# NBBC95.net
KiCad netlist of a schematic drawn in Altium Designer
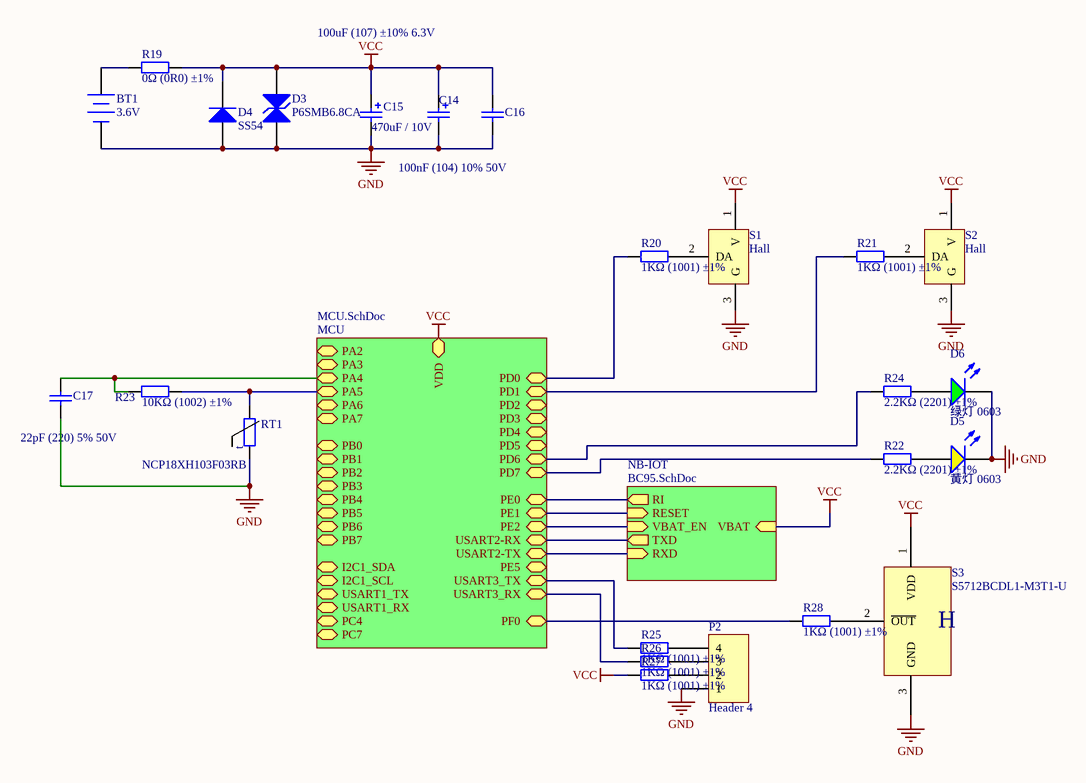
[diagram p0: NBBC95水表.SchDoc]

(export (version "E")
  (design (tool "Eeschema 10.0.6"))
  (components
    (comp (ref "BT1")
      (value "3.6V")
      (footprint "电池连接焊线")
      (description "功率型锂电池")
      (fields (field (name "PUBLISHER") "Altium Limited"))
      (libsource (lib "Miscellaneous Devices") (part "Battery"))
    )
    (comp (ref "C14")
      (value "100uF (107) ±10% 6.3V")
      (footprint "CASE-B_3528")
      (description "钽电容")
      (libsource (lib "Miscellaneous Devices LC") (part "3528 100uF (107) 10% 6.3V"))
    )
    (comp (ref "C15")
      (value "470uF / 10V")
      (footprint "CASE-E_7343")
      (description "钽电容")
      (libsource (lib "CAP") (part "法拉电容 0.5F"))
    )
    (comp (ref "C16")
      (value "100nF (104) 10% 50V")
      (footprint "0603_C")
      (description "贴片电容")
      (libsource (lib "Miscellaneous Devices LC") (part "0603 100nF (104) 10% 50V"))
    )
    (comp (ref "C17")
      (value "22pF (220) 5% 50V")
      (footprint "0603_C")
      (description "贴片电容")
      (libsource (lib "Miscellaneous Devices LC") (part "0603 22pF (220) 5% 50V"))
    )
    (comp (ref "D3")
      (value "P6SMB6.8CA")
      (footprint "SMB(DO-214AA)_S1")
      (description "TVS")
      (libsource (lib "Miscellaneous Devices LC") (part "SMB/DO-214AA P6SMB6.8CA"))
    )
    (comp (ref "D4")
      (value "SS54")
      (footprint "SMA(DO-214AC)_S1")
      (description "二极管")
      (libsource (lib "Miscellaneous Devices LC") (part "SMA(DO-214AC) SS54"))
    )
    (comp (ref "D5")
      (value "黄灯 0603")
      (footprint "0603_LED_S1")
      (description "发光二极管")
      (libsource (lib "Miscellaneous Devices LC") (part "0603 黄灯"))
    )
    (comp (ref "D6")
      (value "绿灯 0603")
      (footprint "0603_LED_S1")
      (description "发光二极管")
      (libsource (lib "Miscellaneous Devices LC") (part "0603 绿灯"))
    )
    (comp (ref "P2")
      (value "Header 4")
      (footprint "HDR1X4")
      (description "Header, 4-Pin")
      (fields (field (name "PUBLISHER") "Altium Limited"))
      (libsource (lib "Miscellaneous Connectors") (part "Header 4"))
    )
    (comp (ref "R19")
      (value "0Ω (0R0) ±1%")
      (footprint "0805_R")
      (description "贴片电阻")
      (libsource (lib "Miscellaneous Devices LC") (part "0805 0Ω (0R0) 1%"))
    )
    (comp (ref "R20")
      (value "1KΩ (1001) ±1%")
      (footprint "0603_R")
      (description "贴片电阻")
      (libsource (lib "Miscellaneous Devices LC") (part "0603 1KΩ (1001) 1%"))
    )
    (comp (ref "R21")
      (value "1KΩ (1001) ±1%")
      (footprint "0603_R")
      (description "贴片电阻")
      (libsource (lib "Miscellaneous Devices LC") (part "0603 1KΩ (1001) 1%"))
    )
    (comp (ref "R22")
      (value "2.2KΩ (2201) ±1%")
      (footprint "0603_R")
      (description "贴片电阻")
      (libsource (lib "Miscellaneous Devices LC") (part "0603 2.2KΩ (2201) 1%"))
    )
    (comp (ref "R23")
      (value "10KΩ (1002) ±1%")
      (footprint "0603_R")
      (description "贴片电阻")
      (libsource (lib "Miscellaneous Devices LC") (part "0603 10KΩ (1002) 1%"))
    )
    (comp (ref "R24")
      (value "2.2KΩ (2201) ±1%")
      (footprint "0603_R")
      (description "贴片电阻")
      (libsource (lib "Miscellaneous Devices LC") (part "0603 2.2KΩ (2201) 1%"))
    )
    (comp (ref "R25")
      (value "1KΩ (1001) ±1%")
      (footprint "0603_R")
      (description "贴片电阻")
      (libsource (lib "") (part "0603 1KΩ (1001) 1%_1"))
    )
    (comp (ref "R26")
      (value "1KΩ (1001) ±1%")
      (footprint "0603_R")
      (description "贴片电阻")
      (libsource (lib "") (part "0603 1KΩ (1001) 1%_1"))
    )
    (comp (ref "R27")
      (value "1KΩ (1001) ±1%")
      (footprint "0603_R")
      (description "贴片电阻")
      (libsource (lib "") (part "0603 1KΩ (1001) 1%_1"))
    )
    (comp (ref "R28")
      (value "1KΩ (1001) ±1%")
      (footprint "0603_R")
      (description "贴片电阻")
      (libsource (lib "Miscellaneous Devices LC") (part "0603 1KΩ (1001) 1%"))
    )
    (comp (ref "RT1")
      (value "NCP18XH103F03RB")
      (footprint "0603_R")
      (description "热敏电阻")
      (libsource (lib "RES") (part "NCP18XH103F03RB"))
    )
    (comp (ref "S1")
      (value "Hall")
      (footprint "霍尔转接板")
      (description "霍尔开关转接板")
      (libsource (lib "NB") (part "霍尔开关转接板"))
    )
    (comp (ref "S2")
      (value "Hall")
      (footprint "霍尔转接板")
      (description "霍尔开关转接板")
      (libsource (lib "NB") (part "霍尔开关转接板"))
    )
    (comp (ref "S3") (value "S5712BCDL1-M3T1-U") (footprint "SOT-23") (libsource (lib "分立元件") (part "S5712")))
  )
  (nets
    (net (code "5") (name "/PA4") (class "Default")
      (node (ref "C17") (pin "2") (pinfunction "2_2") (pintype "passive"))
      (node (ref "R23") (pin "1") (pinfunction "1_1") (pintype "passive"))
    )
    (net (code "6") (name "/PA5") (class "Default")
      (node (ref "R23") (pin "2") (pinfunction "2_2") (pintype "passive"))
      (node (ref "RT1") (pin "2") (pinfunction "2_2") (pintype "passive"))
    )
    (net (code "19") (name "/PD0") (class "Default")
      (node (ref "R20") (pin "1") (pinfunction "1_1") (pintype "passive"))
    )
    (net (code "20") (name "/PD1") (class "Default")
      (node (ref "R21") (pin "1") (pinfunction "1_1") (pintype "passive"))
    )
    (net (code "25") (name "/PD6") (class "Default")
      (node (ref "R24") (pin "1") (pinfunction "1_1") (pintype "passive"))
    )
    (net (code "26") (name "/PD7") (class "Default")
      (node (ref "R22") (pin "1") (pinfunction "1_1") (pintype "passive"))
    )
    (net (code "30") (name "/PF0") (class "Default")
      (node (ref "R28") (pin "1") (pinfunction "1_1") (pintype "passive"))
    )
    (net (code "36") (name "/USART3_RX") (class "Default")
      (node (ref "R26") (pin "2") (pinfunction "2_2") (pintype "passive"))
    )
    (net (code "37") (name "/USART3_TX") (class "Default")
      (node (ref "R25") (pin "2") (pinfunction "2_2") (pintype "passive"))
    )
    (net (code "38") (name "GND") (class "Default")
      (node (ref "BT1") (pin "2") (pinfunction "-_2") (pintype "passive"))
      (node (ref "C14") (pin "2") (pinfunction "2_2") (pintype "passive"))
      (node (ref "C15") (pin "2") (pinfunction "2_2") (pintype "passive"))
      (node (ref "C16") (pin "2") (pinfunction "2_2") (pintype "passive"))
      (node (ref "C17") (pin "1") (pinfunction "1_1") (pintype "passive"))
      (node (ref "D3") (pin "1") (pinfunction "A_1") (pintype "passive"))
      (node (ref "D4") (pin "1") (pinfunction "A_1") (pintype "passive"))
      (node (ref "D5") (pin "K") (pinfunction "K_K") (pintype "passive"))
      (node (ref "D6") (pin "K") (pinfunction "K_K") (pintype "passive"))
      (node (ref "P2") (pin "1") (pinfunction "1_1") (pintype "passive"))
      (node (ref "RT1") (pin "1") (pinfunction "1_1") (pintype "passive"))
      (node (ref "S1") (pin "3") (pinfunction "G_3") (pintype "power_in"))
      (node (ref "S2") (pin "3") (pinfunction "G_3") (pintype "power_in"))
      (node (ref "S3") (pin "3") (pinfunction "GND_3") (pintype "passive"))
    )
    (net (code "39") (name "Net-(BT1-+)") (class "Default")
      (node (ref "BT1") (pin "1") (pinfunction "+_1") (pintype "passive"))
      (node (ref "R19") (pin "1") (pinfunction "1_1") (pintype "passive"))
    )
    (net (code "40") (name "Net-(D5-PadA)") (class "Default")
      (node (ref "D5") (pin "A") (pinfunction "A_A") (pintype "passive"))
      (node (ref "R22") (pin "2") (pinfunction "2_2") (pintype "passive"))
    )
    (net (code "41") (name "Net-(D6-PadA)") (class "Default")
      (node (ref "D6") (pin "A") (pinfunction "A_A") (pintype "passive"))
      (node (ref "R24") (pin "2") (pinfunction "2_2") (pintype "passive"))
    )
    (net (code "42") (name "Net-(P2-Pad2)") (class "Default")
      (node (ref "P2") (pin "2") (pinfunction "2_2") (pintype "passive"))
      (node (ref "R27") (pin "1") (pinfunction "1_1") (pintype "passive"))
    )
    (net (code "43") (name "Net-(P2-Pad3)") (class "Default")
      (node (ref "P2") (pin "3") (pinfunction "3_3") (pintype "passive"))
      (node (ref "R26") (pin "1") (pinfunction "1_1") (pintype "passive"))
    )
    (net (code "44") (name "Net-(P2-Pad4)") (class "Default")
      (node (ref "P2") (pin "4") (pinfunction "4_4") (pintype "passive"))
      (node (ref "R25") (pin "1") (pinfunction "1_1") (pintype "passive"))
    )
    (net (code "45") (name "Net-(S1-DA)") (class "Default")
      (node (ref "R20") (pin "2") (pinfunction "2_2") (pintype "passive"))
      (node (ref "S1") (pin "2") (pinfunction "DA_2") (pintype "passive"))
    )
    (net (code "46") (name "Net-(S2-DA)") (class "Default")
      (node (ref "R21") (pin "2") (pinfunction "2_2") (pintype "passive"))
      (node (ref "S2") (pin "2") (pinfunction "DA_2") (pintype "passive"))
    )
    (net (code "47") (name "Net-(S3-~{OUT})") (class "Default")
      (node (ref "R28") (pin "2") (pinfunction "2_2") (pintype "passive"))
      (node (ref "S3") (pin "2") (pinfunction "~{OUT}_2") (pintype "passive"))
    )
    (net (code "48") (name "VCC") (class "Default")
      (node (ref "C14") (pin "1") (pinfunction "1_1") (pintype "passive"))
      (node (ref "C15") (pin "1") (pinfunction "1_1") (pintype "passive"))
      (node (ref "C16") (pin "1") (pinfunction "1_1") (pintype "passive"))
      (node (ref "D3") (pin "2") (pinfunction "K_2") (pintype "passive"))
      (node (ref "D4") (pin "2") (pinfunction "K_2") (pintype "passive"))
      (node (ref "R19") (pin "2") (pinfunction "2_2") (pintype "passive"))
      (node (ref "R27") (pin "2") (pinfunction "2_2") (pintype "passive"))
      (node (ref "S1") (pin "1") (pinfunction "V_1") (pintype "power_in"))
      (node (ref "S2") (pin "1") (pinfunction "V_1") (pintype "power_in"))
      (node (ref "S3") (pin "1") (pinfunction "VDD_1") (pintype "passive"))
    )
  )
)
